# InitialVersion.net
KiCad netlist of a schematic drawn in EAGLE
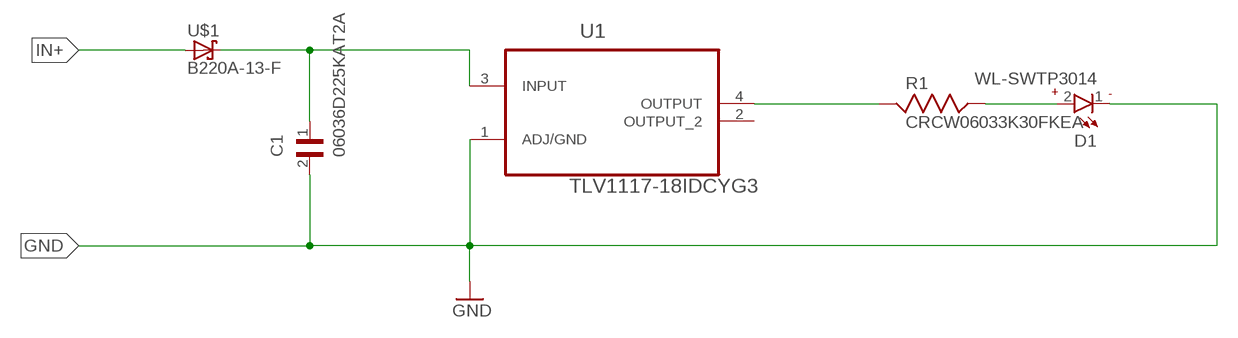
[diagram p0: schematic, sheet 1]

(export (version "E")
  (design (tool "Eeschema 10.0.6"))
  (components
    (comp (ref "C1")
      (value "06036D225KAT2A")
      (footprint "eagle-import:CAPC1608X90")
      (fields (field (name "DIGI-KEY_PART_NUMBER") "478-1252-1-ND") (field (name "MF") "AVX"))
      (libsource (lib "eagle-import") (part "06036D225KAT2A"))
    )
    (comp (ref "D1")
      (value "WL-SWTP3014")
      (footprint "eagle-import:WL-SWTP_3014")
      (fields
        (field (name "DIGI-KEY_PART_NUMBER") "732-5661-1-ND")
        (field (name "MF") "Wurth Electronics")
        (field (name "MP") "158301250")
      )
      (libsource (lib "eagle-import") (part "WL-SWTP3014"))
    )
    (comp (ref "R1")
      (value "CRCW06033K30FKEA")
      (footprint "eagle-import:RESC1608X55")
      (fields (field (name "DIGI-KEY_PART_NUMBER") "541-3.30KHCT-ND") (field (name "MF") "Vishay Dale"))
      (libsource (lib "eagle-import") (part "CRCW06033K30FKEA"))
    )
    (comp (ref "U$1")
      (value "B220A-13-F")
      (footprint "eagle-import:SMA-DIODE")
      (fields (field (name "DIGI-KEY_PART_NUMBER") "B220A-FDICT-ND") (field (name "MF") "Diodes Inc."))
      (libsource (lib "eagle-import") (part "B220A-13-F"))
    )
    (comp (ref "U1")
      (value "TLV1117-18IDCYG3")
      (footprint "eagle-import:SOT230P700X180-4N")
      (fields (field (name "MF") "Texas Instruments"))
      (libsource (lib "eagle-import") (part "TLV1117-18IDCYG3"))
    )
  )
  (nets
    (net (code "1") (name "GND") (class "Default")
      (node (ref "C1") (pin "2") (pinfunction "2_2") (pintype "passive"))
      (node (ref "D1") (pin "1") (pinfunction "1_1") (pintype "bidirectional"))
      (node (ref "U1") (pin "1") (pinfunction "ADJ/GND_1") (pintype "input"))
    )
    (net (code "2") (name "IN+") (class "Default")
      (node (ref "U$1") (pin "1") (pinfunction "A_1") (pintype "passive"))
    )
    (net (code "3") (name "Net-(D1-Pad2)") (class "Default")
      (node (ref "D1") (pin "2") (pinfunction "2_2") (pintype "bidirectional"))
      (node (ref "R1") (pin "2") (pinfunction "2_2") (pintype "passive"))
    )
    (net (code "4") (name "Net-(U$1-C)") (class "Default")
      (node (ref "C1") (pin "1") (pinfunction "1_1") (pintype "passive"))
      (node (ref "U$1") (pin "2") (pinfunction "C_2") (pintype "passive"))
      (node (ref "U1") (pin "3") (pinfunction "INPUT_3") (pintype "input"))
    )
    (net (code "5") (name "Net-(U1-OUTPUT)") (class "Default")
      (node (ref "R1") (pin "1") (pinfunction "1_1") (pintype "passive"))
      (node (ref "U1") (pin "4") (pinfunction "OUTPUT_4") (pintype "output"))
    )
    (net (code "6") (name "unconnected-(U1-OUTPUT_2-Pad2)") (class "Default")
      (node (ref "U1") (pin "2") (pinfunction "OUTPUT_2_2") (pintype "output"))
    )
  )
)
